# LHS.net
KiCad netlist of a schematic drawn in Altium Designer
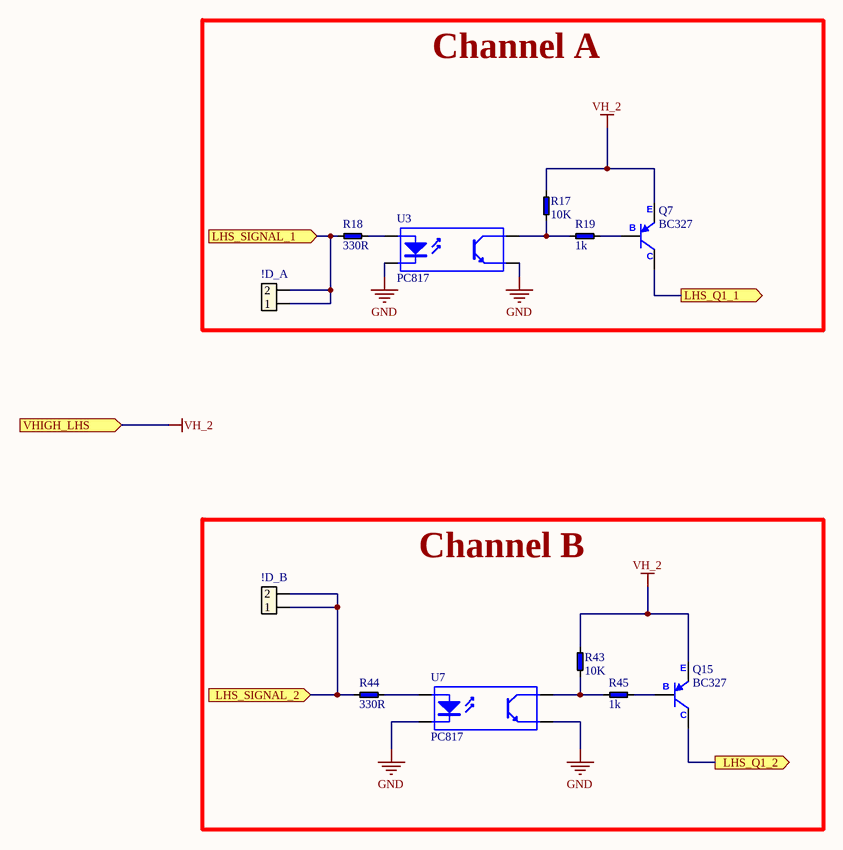
[diagram p0: LHS.SchDoc]

(export (version "E")
  (design (tool "Eeschema 10.0.6"))
  (components
    (comp (ref "!D_A")
      (value "Header 2")
      (footprint "PINHEADER X2")
      (description "Header, 2-Pin")
      (fields (field (name "PUBLISHER") "Altium Limited"))
      (libsource (lib "Altium_Abbas") (part "Header 2"))
    )
    (comp (ref "!D_B")
      (value "Header 2")
      (footprint "PINHEADER X2")
      (description "Header, 2-Pin")
      (fields (field (name "PUBLISHER") "Altium Limited"))
      (libsource (lib "Altium_Abbas") (part "Header 2"))
    )
    (comp (ref "Q7")
      (value "BC327")
      (footprint "Transistor - duplicate3")
      (libsource (lib "Altium_Abbas") (part "PNP"))
    )
    (comp (ref "Q15")
      (value "BC327")
      (footprint "Transistor - duplicate3")
      (libsource (lib "Altium_Abbas") (part "PNP"))
    )
    (comp (ref "R17")
      (value "10K")
      (footprint "RESISTOR _9")
      (libsource (lib "Altium_Abbas") (part "RESISTOR"))
    )
    (comp (ref "R18")
      (value "330R")
      (footprint "RESISTOR _9")
      (libsource (lib "Altium_Abbas") (part "RESISTOR"))
    )
    (comp (ref "R19")
      (value "1k")
      (footprint "RESISTOR _9")
      (libsource (lib "Altium_Abbas") (part "RESISTOR"))
    )
    (comp (ref "R43")
      (value "10K")
      (footprint "RESISTOR _9")
      (libsource (lib "Altium_Abbas") (part "RESISTOR"))
    )
    (comp (ref "R44")
      (value "330R")
      (footprint "RESISTOR _9")
      (libsource (lib "Altium_Abbas") (part "RESISTOR"))
    )
    (comp (ref "R45")
      (value "1k")
      (footprint "RESISTOR _9")
      (libsource (lib "Altium_Abbas") (part "RESISTOR"))
    )
    (comp (ref "U3")
      (value "PC817")
      (footprint "IC X4 PIN")
      (description "4-Pin Phototransistor Optocoupler")
      (fields (field (name "PUBLISHER") "Altium Limited"))
      (libsource (lib "Altium_Abbas") (part "Opto-coupler"))
    )
    (comp (ref "U7")
      (value "PC817")
      (footprint "IC X4 PIN")
      (description "4-Pin Phototransistor Optocoupler")
      (fields (field (name "PUBLISHER") "Altium Limited"))
      (libsource (lib "Altium_Abbas") (part "Opto-coupler"))
    )
  )
  (nets
    (net (code "1") (name "/LHS_Q1_1") (class "Default")
      (node (ref "Q7") (pin "3") (pinfunction "C_3") (pintype "passive"))
    )
    (net (code "2") (name "/LHS_Q1_2") (class "Default")
      (node (ref "Q15") (pin "3") (pinfunction "C_3") (pintype "passive"))
    )
    (net (code "3") (name "/LHS_SIGNAL_1") (class "Default")
      (node (ref "!D_A") (pin "1") (pinfunction "1_1") (pintype "passive"))
      (node (ref "!D_A") (pin "2") (pinfunction "2_2") (pintype "passive"))
      (node (ref "R18") (pin "1") (pinfunction "5_1") (pintype "passive"))
    )
    (net (code "4") (name "/LHS_SIGNAL_2") (class "Default")
      (node (ref "!D_B") (pin "1") (pinfunction "1_1") (pintype "passive"))
      (node (ref "!D_B") (pin "2") (pinfunction "2_2") (pintype "passive"))
      (node (ref "R44") (pin "1") (pinfunction "5_1") (pintype "passive"))
    )
    (net (code "5") (name "GND") (class "Default")
      (node (ref "U3") (pin "2") (pinfunction "K_2") (pintype "passive"))
      (node (ref "U3") (pin "3") (pinfunction "E_3") (pintype "passive"))
      (node (ref "U7") (pin "2") (pinfunction "K_2") (pintype "passive"))
      (node (ref "U7") (pin "3") (pinfunction "E_3") (pintype "passive"))
    )
    (net (code "6") (name "Net-(Q7-B)") (class "Default")
      (node (ref "Q7") (pin "2") (pinfunction "B_2") (pintype "passive"))
      (node (ref "R19") (pin "2") (pinfunction "6_2") (pintype "passive"))
    )
    (net (code "7") (name "Net-(Q15-B)") (class "Default")
      (node (ref "Q15") (pin "2") (pinfunction "B_2") (pintype "passive"))
      (node (ref "R45") (pin "2") (pinfunction "6_2") (pintype "passive"))
    )
    (net (code "8") (name "Net-(R17-6)") (class "Default")
      (node (ref "R17") (pin "2") (pinfunction "6_2") (pintype "passive"))
      (node (ref "R19") (pin "1") (pinfunction "5_1") (pintype "passive"))
      (node (ref "U3") (pin "4") (pinfunction "C_4") (pintype "passive"))
    )
    (net (code "9") (name "Net-(R18-6)") (class "Default")
      (node (ref "R18") (pin "2") (pinfunction "6_2") (pintype "passive"))
      (node (ref "U3") (pin "1") (pinfunction "A_1") (pintype "passive"))
    )
    (net (code "10") (name "Net-(R43-5)") (class "Default")
      (node (ref "R43") (pin "1") (pinfunction "5_1") (pintype "passive"))
      (node (ref "R45") (pin "1") (pinfunction "5_1") (pintype "passive"))
      (node (ref "U7") (pin "4") (pinfunction "C_4") (pintype "passive"))
    )
    (net (code "11") (name "Net-(R44-6)") (class "Default")
      (node (ref "R44") (pin "2") (pinfunction "6_2") (pintype "passive"))
      (node (ref "U7") (pin "1") (pinfunction "A_1") (pintype "passive"))
    )
    (net (code "12") (name "VH_2") (class "Default")
      (node (ref "Q15") (pin "1") (pinfunction "E_1") (pintype "passive"))
      (node (ref "Q7") (pin "1") (pinfunction "E_1") (pintype "passive"))
      (node (ref "R17") (pin "1") (pinfunction "5_1") (pintype "passive"))
      (node (ref "R43") (pin "2") (pinfunction "6_2") (pintype "passive"))
    )
  )
)
